# Sheet1.net
KiCad netlist of a schematic drawn in Altium Designer
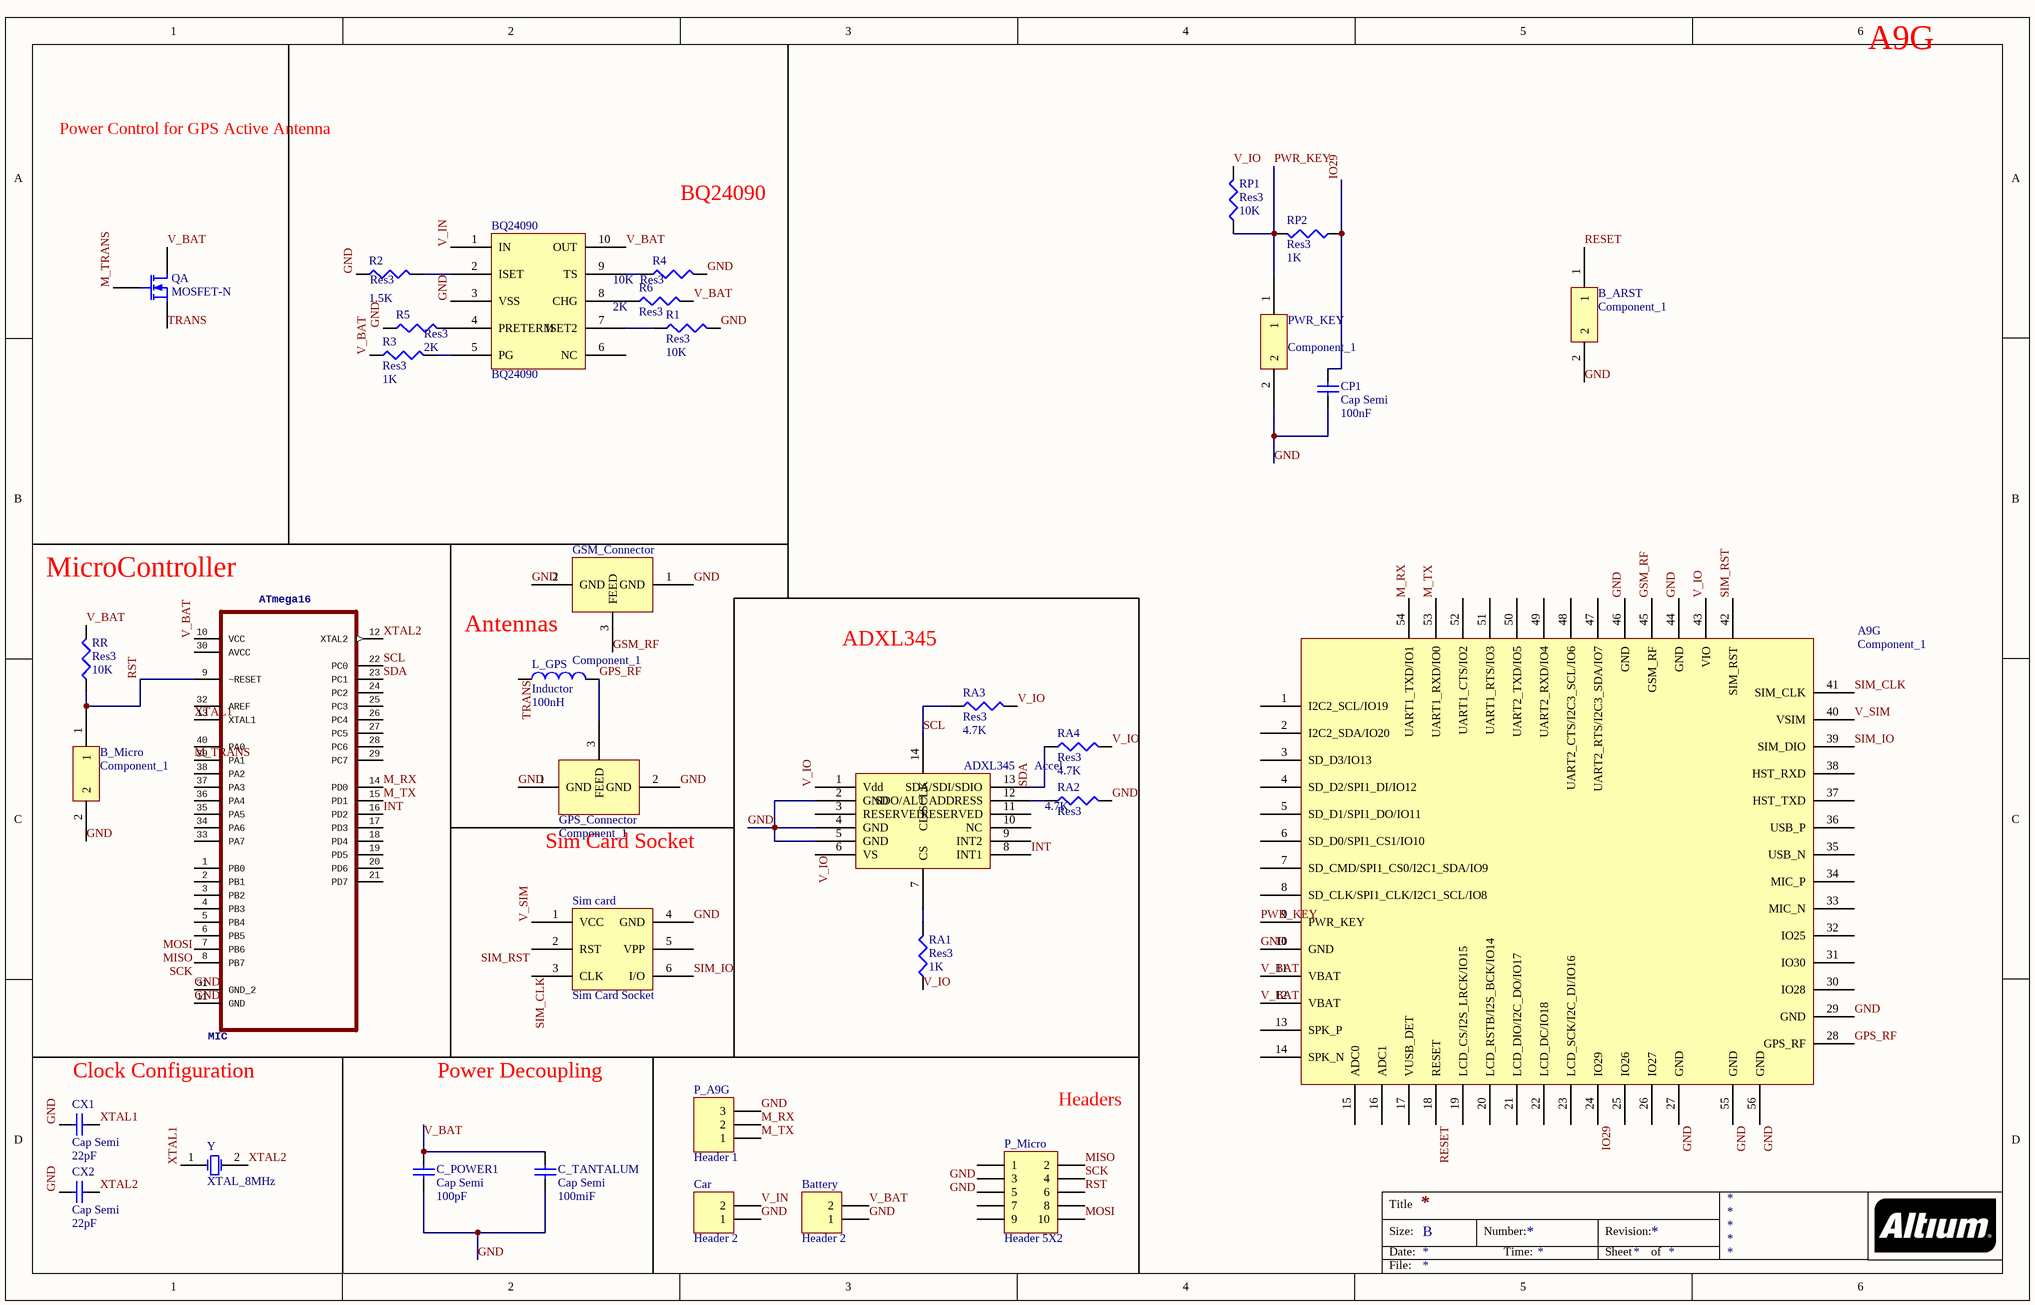
[diagram p0: Sheet1.SchDoc]

(export (version "E")
  (design (tool "Eeschema 10.0.6"))
  (components
    (comp (ref "A9G")
      (value "Component_1")
      (footprint "PCBComponent_1")
      (libsource (lib "A9G_custom") (part "Component_1"))
    )
    (comp (ref "Accel")
      (value "ADXL345")
      (footprint "PCBComponent_1")
      (libsource (lib "KKK") (part "Component_1"))
    )
    (comp (ref "ATmega16")
      (value "MIC")
      (footprint "DIP254P1524X482-40")
      (fields (field (name "MP") "ATMEGA16A-PU") (field (name "MF") "Microchip"))
      (libsource (lib "ATMEGA16A-PU") (part "ATMEGA16A-PU"))
    )
    (comp (ref "Battery")
      (value "Header 2")
      (footprint "HDR1X2")
      (description "Header, 2-Pin")
      (fields (field (name "PUBLISHER") "Altium Limited"))
      (libsource (lib "Miscellaneous Connectors") (part "Header 2"))
    )
    (comp (ref "BQ24090")
      (value "BQ24090")
      (footprint "PCBComponent_1")
      (libsource (lib "BQ24090") (part "Component_1"))
    )
    (comp (ref "B_ARST")
      (value "Component_1")
      (footprint "PCBComponent_1")
      (libsource (lib "SMD_button") (part "Component_1"))
    )
    (comp (ref "B_Micro")
      (value "Component_1")
      (footprint "PCBComponent_1")
      (libsource (lib "SMD_button") (part "Component_1"))
    )
    (comp (ref "Car")
      (value "Header 2")
      (footprint "HDR1X2")
      (description "Header, 2-Pin")
      (fields (field (name "PUBLISHER") "Altium Limited"))
      (libsource (lib "Miscellaneous Connectors") (part "Header 2"))
    )
    (comp (ref "CP1")
      (value "Cap Semi")
      (footprint "1608[0603]")
      (description "Capacitor (Semiconductor SIM Model)")
      (fields (field (name "ALTIUM_VALUE") "100nF") (field (name "PUBLISHER") "Altium Limited"))
      (libsource (lib "Miscellaneous Devices") (part "Cap Semi"))
    )
    (comp (ref "CX1")
      (value "Cap Semi")
      (footprint "1608[0603]")
      (description "Capacitor (Semiconductor SIM Model)")
      (fields (field (name "ALTIUM_VALUE") "22pF") (field (name "PUBLISHER") "Altium Limited"))
      (libsource (lib "Miscellaneous Devices") (part "Cap Semi"))
    )
    (comp (ref "CX2")
      (value "Cap Semi")
      (footprint "1608[0603]")
      (description "Capacitor (Semiconductor SIM Model)")
      (fields (field (name "ALTIUM_VALUE") "22pF") (field (name "PUBLISHER") "Altium Limited"))
      (libsource (lib "Miscellaneous Devices") (part "Cap Semi"))
    )
    (comp (ref "C_POWER1")
      (value "Cap Semi")
      (footprint "1608[0603]")
      (description "Capacitor (Semiconductor SIM Model)")
      (fields (field (name "ALTIUM_VALUE") "100pF") (field (name "PUBLISHER") "Altium Limited"))
      (libsource (lib "Miscellaneous Devices") (part "Cap Semi"))
    )
    (comp (ref "C_TANTALUM")
      (value "Cap Semi")
      (footprint "C1206")
      (description "Capacitor (Semiconductor SIM Model)")
      (fields (field (name "ALTIUM_VALUE") "100miF") (field (name "PUBLISHER") "Altium Limited"))
      (libsource (lib "Miscellaneous Devices") (part "Cap Semi"))
    )
    (comp (ref "GPS_Connector")
      (value "Component_1")
      (footprint "PCBComponent_1")
      (libsource (lib "IPX Cnnector") (part "Component_1"))
    )
    (comp (ref "GSM_Connector")
      (value "Component_1")
      (footprint "PCBComponent_1")
      (libsource (lib "") (part "Component_1_1"))
    )
    (comp (ref "L_GPS")
      (value "Inductor")
      (footprint "0603")
      (fields (field (name "ALTIUM_VALUE") "100nH") (field (name "PUBLISHER") "Altium Limited"))
      (libsource (lib "Miscellaneous Devices") (part "Inductor"))
    )
    (comp (ref "PWR_KEY")
      (value "Component_1")
      (footprint "PCBComponent_1")
      (libsource (lib "SMD_button") (part "Component_1"))
    )
    (comp (ref "P_A9G")
      (value "Header 1")
      (footprint "HDR1X3")
      (description "Header, 3-Pin")
      (fields (field (name "PUBLISHER") "Altium Limited"))
      (libsource (lib "Miscellaneous Connectors") (part "Header 3"))
    )
    (comp (ref "P_Micro")
      (value "Header 5X2")
      (footprint "HDR2X5")
      (description "Header, 5-Pin, Dual row")
      (fields (field (name "PUBLISHER") "Altium Limited"))
      (libsource (lib "Miscellaneous Connectors") (part "Header 5X2"))
    )
    (comp (ref "QA")
      (value "MOSFET-N")
      (footprint "E3")
      (description "N-Channel MOSFET")
      (fields (field (name "PUBLISHER") "Altium Limited"))
      (libsource (lib "Miscellaneous Devices") (part "MOSFET-N"))
    )
    (comp (ref "R1")
      (value "Res3")
      (footprint "J1-0603")
      (description "Resistor")
      (fields (field (name "ALTIUM_VALUE") "10K") (field (name "PUBLISHER") "Altium Limited"))
      (libsource (lib "Miscellaneous Devices") (part "Res3"))
    )
    (comp (ref "R2")
      (value "Res3")
      (footprint "J1-0603")
      (description "Resistor")
      (fields (field (name "ALTIUM_VALUE") "1.5K") (field (name "PUBLISHER") "Altium Limited"))
      (libsource (lib "Miscellaneous Devices") (part "Res3"))
    )
    (comp (ref "R3")
      (value "Res3")
      (footprint "J1-0603")
      (description "Resistor")
      (fields (field (name "ALTIUM_VALUE") "1K") (field (name "PUBLISHER") "Altium Limited"))
      (libsource (lib "Miscellaneous Devices") (part "Res3"))
    )
    (comp (ref "R4")
      (value "Res3")
      (footprint "J1-0603")
      (description "Resistor")
      (fields (field (name "ALTIUM_VALUE") "10K") (field (name "PUBLISHER") "Altium Limited"))
      (libsource (lib "Miscellaneous Devices") (part "Res3"))
    )
    (comp (ref "R5")
      (value "Res3")
      (footprint "J1-0603")
      (description "Resistor")
      (fields (field (name "ALTIUM_VALUE") "2K") (field (name "PUBLISHER") "Altium Limited"))
      (libsource (lib "Miscellaneous Devices") (part "Res3"))
    )
    (comp (ref "R6")
      (value "Res3")
      (footprint "J1-0603")
      (description "Resistor")
      (fields (field (name "ALTIUM_VALUE") "2K") (field (name "PUBLISHER") "Altium Limited"))
      (libsource (lib "Miscellaneous Devices") (part "Res3"))
    )
    (comp (ref "RA1")
      (value "Res3")
      (footprint "J1-0603")
      (description "Resistor")
      (fields (field (name "ALTIUM_VALUE") "1K") (field (name "PUBLISHER") "Altium Limited"))
      (libsource (lib "Miscellaneous Devices") (part "Res3"))
    )
    (comp (ref "RA2")
      (value "Res3")
      (footprint "J1-0603")
      (description "Resistor")
      (fields (field (name "ALTIUM_VALUE") "4.7K") (field (name "PUBLISHER") "Altium Limited"))
      (libsource (lib "Miscellaneous Devices") (part "Res3"))
    )
    (comp (ref "RA3")
      (value "Res3")
      (footprint "J1-0603")
      (description "Resistor")
      (fields (field (name "ALTIUM_VALUE") "4.7K") (field (name "PUBLISHER") "Altium Limited"))
      (libsource (lib "Miscellaneous Devices") (part "Res3"))
    )
    (comp (ref "RA4")
      (value "Res3")
      (footprint "J1-0603")
      (description "Resistor")
      (fields (field (name "ALTIUM_VALUE") "4.7K") (field (name "PUBLISHER") "Altium Limited"))
      (libsource (lib "Miscellaneous Devices") (part "Res3"))
    )
    (comp (ref "RP1")
      (value "Res3")
      (footprint "J1-0603")
      (description "Resistor")
      (fields (field (name "ALTIUM_VALUE") "10K") (field (name "PUBLISHER") "Altium Limited"))
      (libsource (lib "Miscellaneous Devices") (part "Res3"))
    )
    (comp (ref "RP2")
      (value "Res3")
      (footprint "J1-0603")
      (description "Resistor")
      (fields (field (name "ALTIUM_VALUE") "1K") (field (name "PUBLISHER") "Altium Limited"))
      (libsource (lib "Miscellaneous Devices") (part "Res3"))
    )
    (comp (ref "RR")
      (value "Res3")
      (footprint "J1-0603")
      (description "Resistor")
      (fields (field (name "ALTIUM_VALUE") "10K") (field (name "PUBLISHER") "Altium Limited"))
      (libsource (lib "Miscellaneous Devices") (part "Res3"))
    )
    (comp (ref "Sim card")
      (value "Sim Card Socket")
      (footprint "PCBComponent_1")
      (libsource (lib "Sim_Socket") (part "Component_1"))
    )
    (comp (ref "Y")
      (value "XTAL_8MHz")
      (footprint "R38")
      (description "Crystal Oscillator")
      (fields (field (name "PUBLISHER") "Altium Limited"))
      (libsource (lib "Miscellaneous Devices") (part "XTAL"))
    )
  )
  (nets
    (net (code "1") (name "/GND") (class "Default")
      (node (ref "A9G") (pin "10") (pinfunction "GND_10") (pintype "passive"))
      (node (ref "A9G") (pin "27") (pinfunction "GND_27") (pintype "passive"))
      (node (ref "A9G") (pin "29") (pinfunction "GND_29") (pintype "passive"))
      (node (ref "A9G") (pin "44") (pinfunction "GND_44") (pintype "passive"))
      (node (ref "A9G") (pin "46") (pinfunction "GND_46") (pintype "passive"))
      (node (ref "A9G") (pin "55") (pinfunction "GND_55") (pintype "passive"))
      (node (ref "A9G") (pin "56") (pinfunction "GND_56") (pintype "passive"))
      (node (ref "ATmega16") (pin "11") (pinfunction "GND_11") (pintype "passive"))
      (node (ref "ATmega16") (pin "31") (pinfunction "GND_2_31") (pintype "passive"))
      (node (ref "Accel") (pin "2") (pinfunction "GND_2") (pintype "passive"))
      (node (ref "Accel") (pin "4") (pinfunction "GND_4") (pintype "passive"))
      (node (ref "Accel") (pin "5") (pinfunction "GND_5") (pintype "passive"))
      (node (ref "BQ24090") (pin "3") (pinfunction "VSS_3") (pintype "passive"))
      (node (ref "B_ARST") (pin "2") (pinfunction "2_2") (pintype "passive"))
      (node (ref "B_Micro") (pin "2") (pinfunction "2_2") (pintype "passive"))
      (node (ref "Battery") (pin "1") (pinfunction "1_1") (pintype "passive"))
      (node (ref "CP1") (pin "1") (pinfunction "1_1") (pintype "passive"))
      (node (ref "CX1") (pin "1") (pinfunction "1_1") (pintype "passive"))
      (node (ref "CX2") (pin "1") (pinfunction "1_1") (pintype "passive"))
      (node (ref "C_POWER1") (pin "1") (pinfunction "1_1") (pintype "passive"))
      (node (ref "C_TANTALUM") (pin "1") (pinfunction "1_1") (pintype "passive"))
      (node (ref "Car") (pin "1") (pinfunction "1_1") (pintype "passive"))
      (node (ref "GPS_Connector") (pin "1") (pinfunction "GND_1") (pintype "passive"))
      (node (ref "GPS_Connector") (pin "2") (pinfunction "GND_2") (pintype "passive"))
      (node (ref "GSM_Connector") (pin "1") (pinfunction "GND_1") (pintype "passive"))
      (node (ref "GSM_Connector") (pin "2") (pinfunction "GND_2") (pintype "passive"))
      (node (ref "PWR_KEY") (pin "2") (pinfunction "2_2") (pintype "passive"))
      (node (ref "P_A9G") (pin "3") (pinfunction "3_3") (pintype "passive"))
      (node (ref "P_Micro") (pin "1") (pinfunction "1_1") (pintype "passive"))
      (node (ref "P_Micro") (pin "3") (pinfunction "3_3") (pintype "passive"))
      (node (ref "R1") (pin "2") (pinfunction "2_2") (pintype "passive"))
      (node (ref "R2") (pin "1") (pinfunction "1_1") (pintype "passive"))
      (node (ref "R4") (pin "2") (pinfunction "2_2") (pintype "passive"))
      (node (ref "R5") (pin "1") (pinfunction "1_1") (pintype "passive"))
      (node (ref "RA2") (pin "2") (pinfunction "2_2") (pintype "passive"))
      (node (ref "Sim card") (pin "4") (pinfunction "GND_4") (pintype "passive"))
    )
    (net (code "2") (name "/GPS_RF") (class "Default")
      (node (ref "A9G") (pin "28") (pinfunction "GPS_RF_28") (pintype "passive"))
      (node (ref "GPS_Connector") (pin "3") (pinfunction "FEED_3") (pintype "passive"))
      (node (ref "L_GPS") (pin "2") (pinfunction "2_2") (pintype "passive"))
    )
    (net (code "3") (name "/GSM_RF") (class "Default")
      (node (ref "A9G") (pin "45") (pinfunction "GSM_RF_45") (pintype "passive"))
      (node (ref "GSM_Connector") (pin "3") (pinfunction "FEED_3") (pintype "passive"))
    )
    (net (code "4") (name "/INT") (class "Default")
      (node (ref "ATmega16") (pin "16") (pinfunction "PD2_16") (pintype "passive"))
      (node (ref "Accel") (pin "8") (pinfunction "INT1_8") (pintype "passive"))
    )
    (net (code "5") (name "/IO29") (class "Default")
      (node (ref "A9G") (pin "24") (pinfunction "IO29_24") (pintype "passive"))
      (node (ref "CP1") (pin "2") (pinfunction "2_2") (pintype "passive"))
      (node (ref "RP2") (pin "1") (pinfunction "1_1") (pintype "passive"))
    )
    (net (code "6") (name "/MISO") (class "Default")
      (node (ref "ATmega16") (pin "7") (pinfunction "PB6_7") (pintype "passive"))
      (node (ref "P_Micro") (pin "2") (pinfunction "2_2") (pintype "passive"))
    )
    (net (code "7") (name "/MOSI") (class "Default")
      (node (ref "ATmega16") (pin "6") (pinfunction "PB5_6") (pintype "passive"))
      (node (ref "P_Micro") (pin "10") (pinfunction "10_10") (pintype "passive"))
    )
    (net (code "8") (name "/M_RX") (class "Default")
      (node (ref "A9G") (pin "54") (pinfunction "UART1_TXD/IO1_54") (pintype "passive"))
      (node (ref "ATmega16") (pin "14") (pinfunction "PD0_14") (pintype "passive"))
      (node (ref "P_A9G") (pin "2") (pinfunction "2_2") (pintype "passive"))
    )
    (net (code "9") (name "/M_TRANS") (class "Default")
      (node (ref "ATmega16") (pin "39") (pinfunction "PA1_39") (pintype "passive"))
      (node (ref "QA") (pin "2") (pinfunction "G_2") (pintype "passive"))
    )
    (net (code "10") (name "/M_TX") (class "Default")
      (node (ref "A9G") (pin "53") (pinfunction "UART1_RXD/IO0_53") (pintype "passive"))
      (node (ref "ATmega16") (pin "15") (pinfunction "PD1_15") (pintype "passive"))
      (node (ref "P_A9G") (pin "1") (pinfunction "1_1") (pintype "passive"))
    )
    (net (code "11") (name "/PWR_KEY") (class "Default")
      (node (ref "A9G") (pin "9") (pinfunction "PWR_KEY_9") (pintype "passive"))
      (node (ref "PWR_KEY") (pin "1") (pinfunction "1_1") (pintype "passive"))
      (node (ref "RP1") (pin "1") (pinfunction "1_1") (pintype "passive"))
      (node (ref "RP2") (pin "2") (pinfunction "2_2") (pintype "passive"))
    )
    (net (code "12") (name "/RESET") (class "Default")
      (node (ref "A9G") (pin "18") (pinfunction "RESET_18") (pintype "passive"))
      (node (ref "B_ARST") (pin "1") (pinfunction "1_1") (pintype "passive"))
    )
    (net (code "13") (name "/RST") (class "Default")
      (node (ref "ATmega16") (pin "9") (pinfunction "~RESET_9") (pintype "passive"))
      (node (ref "B_Micro") (pin "1") (pinfunction "1_1") (pintype "passive"))
      (node (ref "P_Micro") (pin "6") (pinfunction "6_6") (pintype "passive"))
      (node (ref "RR") (pin "1") (pinfunction "1_1") (pintype "passive"))
    )
    (net (code "14") (name "/SCK") (class "Default")
      (node (ref "ATmega16") (pin "8") (pinfunction "PB7_8") (pintype "passive"))
      (node (ref "P_Micro") (pin "4") (pinfunction "4_4") (pintype "passive"))
    )
    (net (code "15") (name "/SCL") (class "Default")
      (node (ref "ATmega16") (pin "22") (pinfunction "PC0_22") (pintype "passive"))
      (node (ref "Accel") (pin "14") (pinfunction "CL/SCLK_14") (pintype "passive"))
      (node (ref "RA3") (pin "1") (pinfunction "1_1") (pintype "passive"))
    )
    (net (code "16") (name "/SDA") (class "Default")
      (node (ref "ATmega16") (pin "23") (pinfunction "PC1_23") (pintype "passive"))
      (node (ref "Accel") (pin "13") (pinfunction "SDA/SDI/SDIO_13") (pintype "passive"))
      (node (ref "RA4") (pin "1") (pinfunction "1_1") (pintype "passive"))
    )
    (net (code "17") (name "/SIM_CLK") (class "Default")
      (node (ref "A9G") (pin "41") (pinfunction "SIM_CLK_41") (pintype "passive"))
      (node (ref "Sim card") (pin "3") (pinfunction "CLK_3") (pintype "passive"))
    )
    (net (code "18") (name "/SIM_IO") (class "Default")
      (node (ref "A9G") (pin "39") (pinfunction "SIM_DIO_39") (pintype "passive"))
      (node (ref "Sim card") (pin "6") (pinfunction "I/O_6") (pintype "passive"))
    )
    (net (code "19") (name "/SIM_RST") (class "Default")
      (node (ref "A9G") (pin "42") (pinfunction "SIM_RST_42") (pintype "passive"))
      (node (ref "Sim card") (pin "2") (pinfunction "RST_2") (pintype "passive"))
    )
    (net (code "20") (name "/TRANS") (class "Default")
      (node (ref "L_GPS") (pin "1") (pinfunction "1_1") (pintype "passive"))
      (node (ref "QA") (pin "3") (pinfunction "S_3") (pintype "passive"))
    )
    (net (code "21") (name "/V_BAT") (class "Default")
      (node (ref "A9G") (pin "11") (pinfunction "VBAT_11") (pintype "passive"))
      (node (ref "A9G") (pin "12") (pinfunction "VBAT_12") (pintype "passive"))
      (node (ref "ATmega16") (pin "10") (pinfunction "VCC_10") (pintype "power_in"))
      (node (ref "BQ24090") (pin "10") (pinfunction "OUT_10") (pintype "passive"))
      (node (ref "Battery") (pin "2") (pinfunction "2_2") (pintype "passive"))
      (node (ref "C_POWER1") (pin "2") (pinfunction "2_2") (pintype "passive"))
      (node (ref "C_TANTALUM") (pin "2") (pinfunction "2_2") (pintype "passive"))
      (node (ref "QA") (pin "1") (pinfunction "D_1") (pintype "passive"))
      (node (ref "R3") (pin "1") (pinfunction "1_1") (pintype "passive"))
      (node (ref "R6") (pin "2") (pinfunction "2_2") (pintype "passive"))
      (node (ref "RR") (pin "2") (pinfunction "2_2") (pintype "passive"))
    )
    (net (code "22") (name "/V_IN") (class "Default")
      (node (ref "BQ24090") (pin "1") (pinfunction "IN_1") (pintype "passive"))
      (node (ref "Car") (pin "2") (pinfunction "2_2") (pintype "passive"))
    )
    (net (code "23") (name "/V_IO") (class "Default")
      (node (ref "A9G") (pin "43") (pinfunction "VIO_43") (pintype "passive"))
      (node (ref "Accel") (pin "1") (pinfunction "Vdd_1") (pintype "passive"))
      (node (ref "Accel") (pin "6") (pinfunction "VS_6") (pintype "passive"))
      (node (ref "RA1") (pin "1") (pinfunction "1_1") (pintype "passive"))
      (node (ref "RA3") (pin "2") (pinfunction "2_2") (pintype "passive"))
      (node (ref "RA4") (pin "2") (pinfunction "2_2") (pintype "passive"))
      (node (ref "RP1") (pin "2") (pinfunction "2_2") (pintype "passive"))
    )
    (net (code "24") (name "/V_SIM") (class "Default")
      (node (ref "A9G") (pin "40") (pinfunction "VSIM_40") (pintype "passive"))
      (node (ref "Sim card") (pin "1") (pinfunction "VCC_1") (pintype "passive"))
    )
    (net (code "25") (name "/XTAL1") (class "Default")
      (node (ref "ATmega16") (pin "13") (pinfunction "XTAL1_13") (pintype "passive"))
      (node (ref "CX1") (pin "2") (pinfunction "2_2") (pintype "passive"))
      (node (ref "Y") (pin "1") (pinfunction "OSC1_1") (pintype "passive"))
    )
    (net (code "26") (name "/XTAL2") (class "Default")
      (node (ref "ATmega16") (pin "12") (pinfunction "XTAL2_12") (pintype "output"))
      (node (ref "CX2") (pin "2") (pinfunction "2_2") (pintype "passive"))
      (node (ref "Y") (pin "2") (pinfunction "OSC2_2") (pintype "passive"))
    )
    (net (code "27") (name "Net-(Accel-CS)") (class "Default")
      (node (ref "Accel") (pin "7") (pinfunction "CS_7") (pintype "passive"))
      (node (ref "RA1") (pin "2") (pinfunction "2_2") (pintype "passive"))
    )
    (net (code "28") (name "Net-(Accel-SDO{slash}ALT_ADDRESS)") (class "Default")
      (node (ref "Accel") (pin "12") (pinfunction "SDO/ALT_ADDRESS_12") (pintype "passive"))
      (node (ref "RA2") (pin "1") (pinfunction "1_1") (pintype "passive"))
    )
    (net (code "29") (name "Net-(BQ24090-CHG)") (class "Default")
      (node (ref "BQ24090") (pin "8") (pinfunction "CHG_8") (pintype "passive"))
      (node (ref "R6") (pin "1") (pinfunction "1_1") (pintype "passive"))
    )
    (net (code "30") (name "Net-(BQ24090-ISET)") (class "Default")
      (node (ref "BQ24090") (pin "2") (pinfunction "ISET_2") (pintype "passive"))
      (node (ref "R2") (pin "2") (pinfunction "2_2") (pintype "passive"))
    )
    (net (code "31") (name "Net-(BQ24090-ISET2)") (class "Default")
      (node (ref "BQ24090") (pin "7") (pinfunction "ISET2_7") (pintype "passive"))
      (node (ref "R1") (pin "1") (pinfunction "1_1") (pintype "passive"))
    )
    (net (code "32") (name "Net-(BQ24090-PG)") (class "Default")
      (node (ref "BQ24090") (pin "5") (pinfunction "PG_5") (pintype "passive"))
      (node (ref "R3") (pin "2") (pinfunction "2_2") (pintype "passive"))
    )
    (net (code "33") (name "Net-(BQ24090-PRETERM)") (class "Default")
      (node (ref "BQ24090") (pin "4") (pinfunction "PRETERM_4") (pintype "passive"))
      (node (ref "R5") (pin "2") (pinfunction "2_2") (pintype "passive"))
    )
    (net (code "34") (name "Net-(BQ24090-TS)") (class "Default")
      (node (ref "BQ24090") (pin "9") (pinfunction "TS_9") (pintype "passive"))
      (node (ref "R4") (pin "1") (pinfunction "1_1") (pintype "passive"))
    )
    (net (code "35") (name "unconnected-(A9G-ADC0-Pad15)") (class "Default")
      (node (ref "A9G") (pin "15") (pinfunction "ADC0_15") (pintype "passive"))
    )
    (net (code "36") (name "unconnected-(A9G-ADC1-Pad16)") (class "Default")
      (node (ref "A9G") (pin "16") (pinfunction "ADC1_16") (pintype "passive"))
    )
    (net (code "37") (name "unconnected-(A9G-HST_RXD-Pad38)") (class "Default")
      (node (ref "A9G") (pin "38") (pinfunction "HST_RXD_38") (pintype "passive"))
    )
    (net (code "38") (name "unconnected-(A9G-HST_TXD-Pad37)") (class "Default")
      (node (ref "A9G") (pin "37") (pinfunction "HST_TXD_37") (pintype "passive"))
    )
    (net (code "39") (name "unconnected-(A9G-I2C2_SCL{slash}IO19-Pad1)") (class "Default")
      (node (ref "A9G") (pin "1") (pinfunction "I2C2_SCL/IO19_1") (pintype "passive"))
    )
    (net (code "40") (name "unconnected-(A9G-I2C2_SDA{slash}IO20-Pad2)") (class "Default")
      (node (ref "A9G") (pin "2") (pinfunction "I2C2_SDA/IO20_2") (pintype "passive"))
    )
    (net (code "41") (name "unconnected-(A9G-IO25-Pad32)") (class "Default")
      (node (ref "A9G") (pin "32") (pinfunction "IO25_32") (pintype "passive"))
    )
    (net (code "42") (name "unconnected-(A9G-IO26-Pad25)") (class "Default")
      (node (ref "A9G") (pin "25") (pinfunction "IO26_25") (pintype "passive"))
    )
    (net (code "43") (name "unconnected-(A9G-IO27-Pad26)") (class "Default")
      (node (ref "A9G") (pin "26") (pinfunction "IO27_26") (pintype "passive"))
    )
    (net (code "44") (name "unconnected-(A9G-IO28-Pad30)") (class "Default")
      (node (ref "A9G") (pin "30") (pinfunction "IO28_30") (pintype "passive"))
    )
    (net (code "45") (name "unconnected-(A9G-IO30-Pad31)") (class "Default")
      (node (ref "A9G") (pin "31") (pinfunction "IO30_31") (pintype "passive"))
    )
    (net (code "46") (name "unconnected-(A9G-LCD_CS{slash}I2S_LRCK{slash}IO15-Pad19)") (class "Default")
      (node (ref "A9G") (pin "19") (pinfunction "LCD_CS/I2S_LRCK/IO15_19") (pintype "passive"))
    )
    (net (code "47") (name "unconnected-(A9G-LCD_DC{slash}IO18-Pad22)") (class "Default")
      (node (ref "A9G") (pin "22") (pinfunction "LCD_DC/IO18_22") (pintype "passive"))
    )
    (net (code "48") (name "unconnected-(A9G-LCD_DIO{slash}I2C_DO{slash}IO17-Pad21)") (class "Default")
      (node (ref "A9G") (pin "21") (pinfunction "LCD_DIO/I2C_DO/IO17_21") (pintype "passive"))
    )
    (net (code "49") (name "unconnected-(A9G-LCD_RSTB{slash}I2S_BCK{slash}IO14-Pad20)") (class "Default")
      (node (ref "A9G") (pin "20") (pinfunction "LCD_RSTB/I2S_BCK/IO14_20") (pintype "passive"))
    )
    (net (code "50") (name "unconnected-(A9G-LCD_SCK{slash}I2C_DI{slash}IO16-Pad23)") (class "Default")
      (node (ref "A9G") (pin "23") (pinfunction "LCD_SCK/I2C_DI/IO16_23") (pintype "passive"))
    )
    (net (code "51") (name "unconnected-(A9G-MIC_N-Pad33)") (class "Default")
      (node (ref "A9G") (pin "33") (pinfunction "MIC_N_33") (pintype "passive"))
    )
    (net (code "52") (name "unconnected-(A9G-MIC_P-Pad34)") (class "Default")
      (node (ref "A9G") (pin "34") (pinfunction "MIC_P_34") (pintype "passive"))
    )
    (net (code "53") (name "unconnected-(A9G-SD_CLK{slash}SPI1_CLK{slash}I2C1_SCL{slash}IO8-Pad8)") (class "Default")
      (node (ref "A9G") (pin "8") (pinfunction "SD_CLK/SPI1_CLK/I2C1_SCL/IO8_8") (pintype "passive"))
    )
    (net (code "54") (name "unconnected-(A9G-SD_CMD{slash}SPI1_CS0{slash}I2C1_SDA{slash}IO9-Pad7)") (class "Default")
      (node (ref "A9G") (pin "7") (pinfunction "SD_CMD/SPI1_CS0/I2C1_SDA/IO9_7") (pintype "passive"))
    )
    (net (code "55") (name "unconnected-(A9G-SD_D0{slash}SPI1_CS1{slash}IO10-Pad6)") (class "Default")
      (node (ref "A9G") (pin "6") (pinfunction "SD_D0/SPI1_CS1/IO10_6") (pintype "passive"))
    )
    (net (code "56") (name "unconnected-(A9G-SD_D1{slash}SPI1_DO{slash}IO11-Pad5)") (class "Default")
      (node (ref "A9G") (pin "5") (pinfunction "SD_D1/SPI1_DO/IO11_5") (pintype "passive"))
    )
    (net (code "57") (name "unconnected-(A9G-SD_D2{slash}SPI1_DI{slash}IO12-Pad4)") (class "Default")
      (node (ref "A9G") (pin "4") (pinfunction "SD_D2/SPI1_DI/IO12_4") (pintype "passive"))
    )
    (net (code "58") (name "unconnected-(A9G-SD_D3{slash}IO13-Pad3)") (class "Default")
      (node (ref "A9G") (pin "3") (pinfunction "SD_D3/IO13_3") (pintype "passive"))
    )
    (net (code "59") (name "unconnected-(A9G-SPK_N-Pad14)") (class "Default")
      (node (ref "A9G") (pin "14") (pinfunction "SPK_N_14") (pintype "passive"))
    )
    (net (code "60") (name "unconnected-(A9G-SPK_P-Pad13)") (class "Default")
      (node (ref "A9G") (pin "13") (pinfunction "SPK_P_13") (pintype "passive"))
    )
    (net (code "61") (name "unconnected-(A9G-UART1_CTS{slash}IO2-Pad52)") (class "Default")
      (node (ref "A9G") (pin "52") (pinfunction "UART1_CTS/IO2_52") (pintype "passive"))
    )
    (net (code "62") (name "unconnected-(A9G-UART1_RTS{slash}IO3-Pad51)") (class "Default")
      (node (ref "A9G") (pin "51") (pinfunction "UART1_RTS/IO3_51") (pintype "passive"))
    )
    (net (code "63") (name "unconnected-(A9G-UART2_CTS{slash}I2C3_SCL{slash}IO6-Pad48)") (class "Default")
      (node (ref "A9G") (pin "48") (pinfunction "UART2_CTS/I2C3_SCL/IO6_48") (pintype "passive"))
    )
    (net (code "64") (name "unconnected-(A9G-UART2_RTS{slash}I2C3_SDA{slash}IO7-Pad47)") (class "Default")
      (node (ref "A9G") (pin "47") (pinfunction "UART2_RTS/I2C3_SDA/IO7_47") (pintype "passive"))
    )
    (net (code "65") (name "unconnected-(A9G-UART2_RXD{slash}IO4-Pad49)") (class "Default")
      (node (ref "A9G") (pin "49") (pinfunction "UART2_RXD/IO4_49") (pintype "passive"))
    )
    (net (code "66") (name "unconnected-(A9G-UART2_TXD{slash}IO5-Pad50)") (class "Default")
      (node (ref "A9G") (pin "50") (pinfunction "UART2_TXD/IO5_50") (pintype "passive"))
    )
    (net (code "67") (name "unconnected-(A9G-USB_N-Pad35)") (class "Default")
      (node (ref "A9G") (pin "35") (pinfunction "USB_N_35") (pintype "passive"))
    )
    (net (code "68") (name "unconnected-(A9G-USB_P-Pad36)") (class "Default")
      (node (ref "A9G") (pin "36") (pinfunction "USB_P_36") (pintype "passive"))
    )
    (net (code "69") (name "unconnected-(A9G-VUSB_DET-Pad17)") (class "Default")
      (node (ref "A9G") (pin "17") (pinfunction "VUSB_DET_17") (pintype "passive"))
    )
    (net (code "70") (name "unconnected-(ATmega16-AREF-Pad32)") (class "Default")
      (node (ref "ATmega16") (pin "32") (pinfunction "AREF_32") (pintype "passive"))
    )
    (net (code "71") (name "unconnected-(ATmega16-AVCC-Pad30)") (class "Default")
      (node (ref "ATmega16") (pin "30") (pinfunction "AVCC_30") (pintype "power_in"))
    )
    (net (code "72") (name "unconnected-(ATmega16-PA0-Pad40)") (class "Default")
      (node (ref "ATmega16") (pin "40") (pinfunction "PA0_40") (pintype "passive"))
    )
    (net (code "73") (name "unconnected-(ATmega16-PA2-Pad38)") (class "Default")
      (node (ref "ATmega16") (pin "38") (pinfunction "PA2_38") (pintype "passive"))
    )
    (net (code "74") (name "unconnected-(ATmega16-PA3-Pad37)") (class "Default")
      (node (ref "ATmega16") (pin "37") (pinfunction "PA3_37") (pintype "passive"))
    )
    (net (code "75") (name "unconnected-(ATmega16-PA4-Pad36)") (class "Default")
      (node (ref "ATmega16") (pin "36") (pinfunction "PA4_36") (pintype "passive"))
    )
    (net (code "76") (name "unconnected-(ATmega16-PA5-Pad35)") (class "Default")
      (node (ref "ATmega16") (pin "35") (pinfunction "PA5_35") (pintype "passive"))
    )
    (net (code "77") (name "unconnected-(ATmega16-PA6-Pad34)") (class "Default")
      (node (ref "ATmega16") (pin "34") (pinfunction "PA6_34") (pintype "passive"))
    )
    (net (code "78") (name "unconnected-(ATmega16-PA7-Pad33)") (class "Default")
      (node (ref "ATmega16") (pin "33") (pinfunction "PA7_33") (pintype "passive"))
    )
    (net (code "79") (name "unconnected-(ATmega16-PB0-Pad1)") (class "Default")
      (node (ref "ATmega16") (pin "1") (pinfunction "PB0_1") (pintype "passive"))
    )
    (net (code "80") (name "unconnected-(ATmega16-PB1-Pad2)") (class "Default")
      (node (ref "ATmega16") (pin "2") (pinfunction "PB1_2") (pintype "passive"))
    )
    (net (code "81") (name "unconnected-(ATmega16-PB2-Pad3)") (class "Default")
      (node (ref "ATmega16") (pin "3") (pinfunction "PB2_3") (pintype "passive"))
    )
    (net (code "82") (name "unconnected-(ATmega16-PB3-Pad4)") (class "Default")
      (node (ref "ATmega16") (pin "4") (pinfunction "PB3_4") (pintype "passive"))
    )
    (net (code "83") (name "unconnected-(ATmega16-PB4-Pad5)") (class "Default")
      (node (ref "ATmega16") (pin "5") (pinfunction "PB4_5") (pintype "passive"))
    )
    (net (code "84") (name "unconnected-(ATmega16-PC2-Pad24)") (class "Default")
      (node (ref "ATmega16") (pin "24") (pinfunction "PC2_24") (pintype "passive"))
    )
    (net (code "85") (name "unconnected-(ATmega16-PC3-Pad25)") (class "Default")
      (node (ref "ATmega16") (pin "25") (pinfunction "PC3_25") (pintype "passive"))
    )
    (net (code "86") (name "unconnected-(ATmega16-PC4-Pad26)") (class "Default")
      (node (ref "ATmega16") (pin "26") (pinfunction "PC4_26") (pintype "passive"))
    )
    (net (code "87") (name "unconnected-(ATmega16-PC5-Pad27)") (class "Default")
      (node (ref "ATmega16") (pin "27") (pinfunction "PC5_27") (pintype "passive"))
    )
    (net (code "88") (name "unconnected-(ATmega16-PC6-Pad28)") (class "Default")
      (node (ref "ATmega16") (pin "28") (pinfunction "PC6_28") (pintype "passive"))
    )
    (net (code "89") (name "unconnected-(ATmega16-PC7-Pad29)") (class "Default")
      (node (ref "ATmega16") (pin "29") (pinfunction "PC7_29") (pintype "passive"))
    )
    (net (code "90") (name "unconnected-(ATmega16-PD3-Pad17)") (class "Default")
      (node (ref "ATmega16") (pin "17") (pinfunction "PD3_17") (pintype "passive"))
    )
    (net (code "91") (name "unconnected-(ATmega16-PD4-Pad18)") (class "Default")
      (node (ref "ATmega16") (pin "18") (pinfunction "PD4_18") (pintype "passive"))
    )
    (net (code "92") (name "unconnected-(ATmega16-PD5-Pad19)") (class "Default")
      (node (ref "ATmega16") (pin "19") (pinfunction "PD5_19") (pintype "passive"))
    )
    (net (code "93") (name "unconnected-(ATmega16-PD6-Pad20)") (class "Default")
      (node (ref "ATmega16") (pin "20") (pinfunction "PD6_20") (pintype "passive"))
    )
    (net (code "94") (name "unconnected-(ATmega16-PD7-Pad21)") (class "Default")
      (node (ref "ATmega16") (pin "21") (pinfunction "PD7_21") (pintype "passive"))
    )
    (net (code "95") (name "unconnected-(Accel-INT2-Pad9)") (class "Default")
      (node (ref "Accel") (pin "9") (pinfunction "INT2_9") (pintype "passive"))
    )
    (net (code "96") (name "unconnected-(Accel-NC-Pad10)") (class "Default")
      (node (ref "Accel") (pin "10") (pinfunction "NC_10") (pintype "passive"))
    )
    (net (code "97") (name "unconnected-(Accel-RESERVED-Pad3)") (class "Default")
      (node (ref "Accel") (pin "3") (pinfunction "RESERVED_3") (pintype "passive"))
    )
    (net (code "98") (name "unconnected-(Accel-RESERVED-Pad11)") (class "Default")
      (node (ref "Accel") (pin "11") (pinfunction "RESERVED_11") (pintype "passive"))
    )
    (net (code "99") (name "unconnected-(BQ24090-NC-Pad6)") (class "Default")
      (node (ref "BQ24090") (pin "6") (pinfunction "NC_6") (pintype "passive"))
    )
    (net (code "100") (name "unconnected-(P_Micro-Pad5)") (class "Default")
      (node (ref "P_Micro") (pin "5") (pinfunction "5_5") (pintype "passive"))
    )
    (net (code "101") (name "unconnected-(P_Micro-Pad7)") (class "Default")
      (node (ref "P_Micro") (pin "7") (pinfunction "7_7") (pintype "passive"))
    )
    (net (code "102") (name "unconnected-(P_Micro-Pad8)") (class "Default")
      (node (ref "P_Micro") (pin "8") (pinfunction "8_8") (pintype "passive"))
    )
    (net (code "103") (name "unconnected-(P_Micro-Pad9)") (class "Default")
      (node (ref "P_Micro") (pin "9") (pinfunction "9_9") (pintype "passive"))
    )
    (net (code "104") (name "unconnected-(Sim card-VPP-Pad5)") (class "Default")
      (node (ref "Sim card") (pin "5") (pinfunction "VPP_5") (pintype "passive"))
    )
  )
)
